# sparkfun-mlx90640-qwiic-breakout.net
KiCad netlist of a schematic drawn in EAGLE
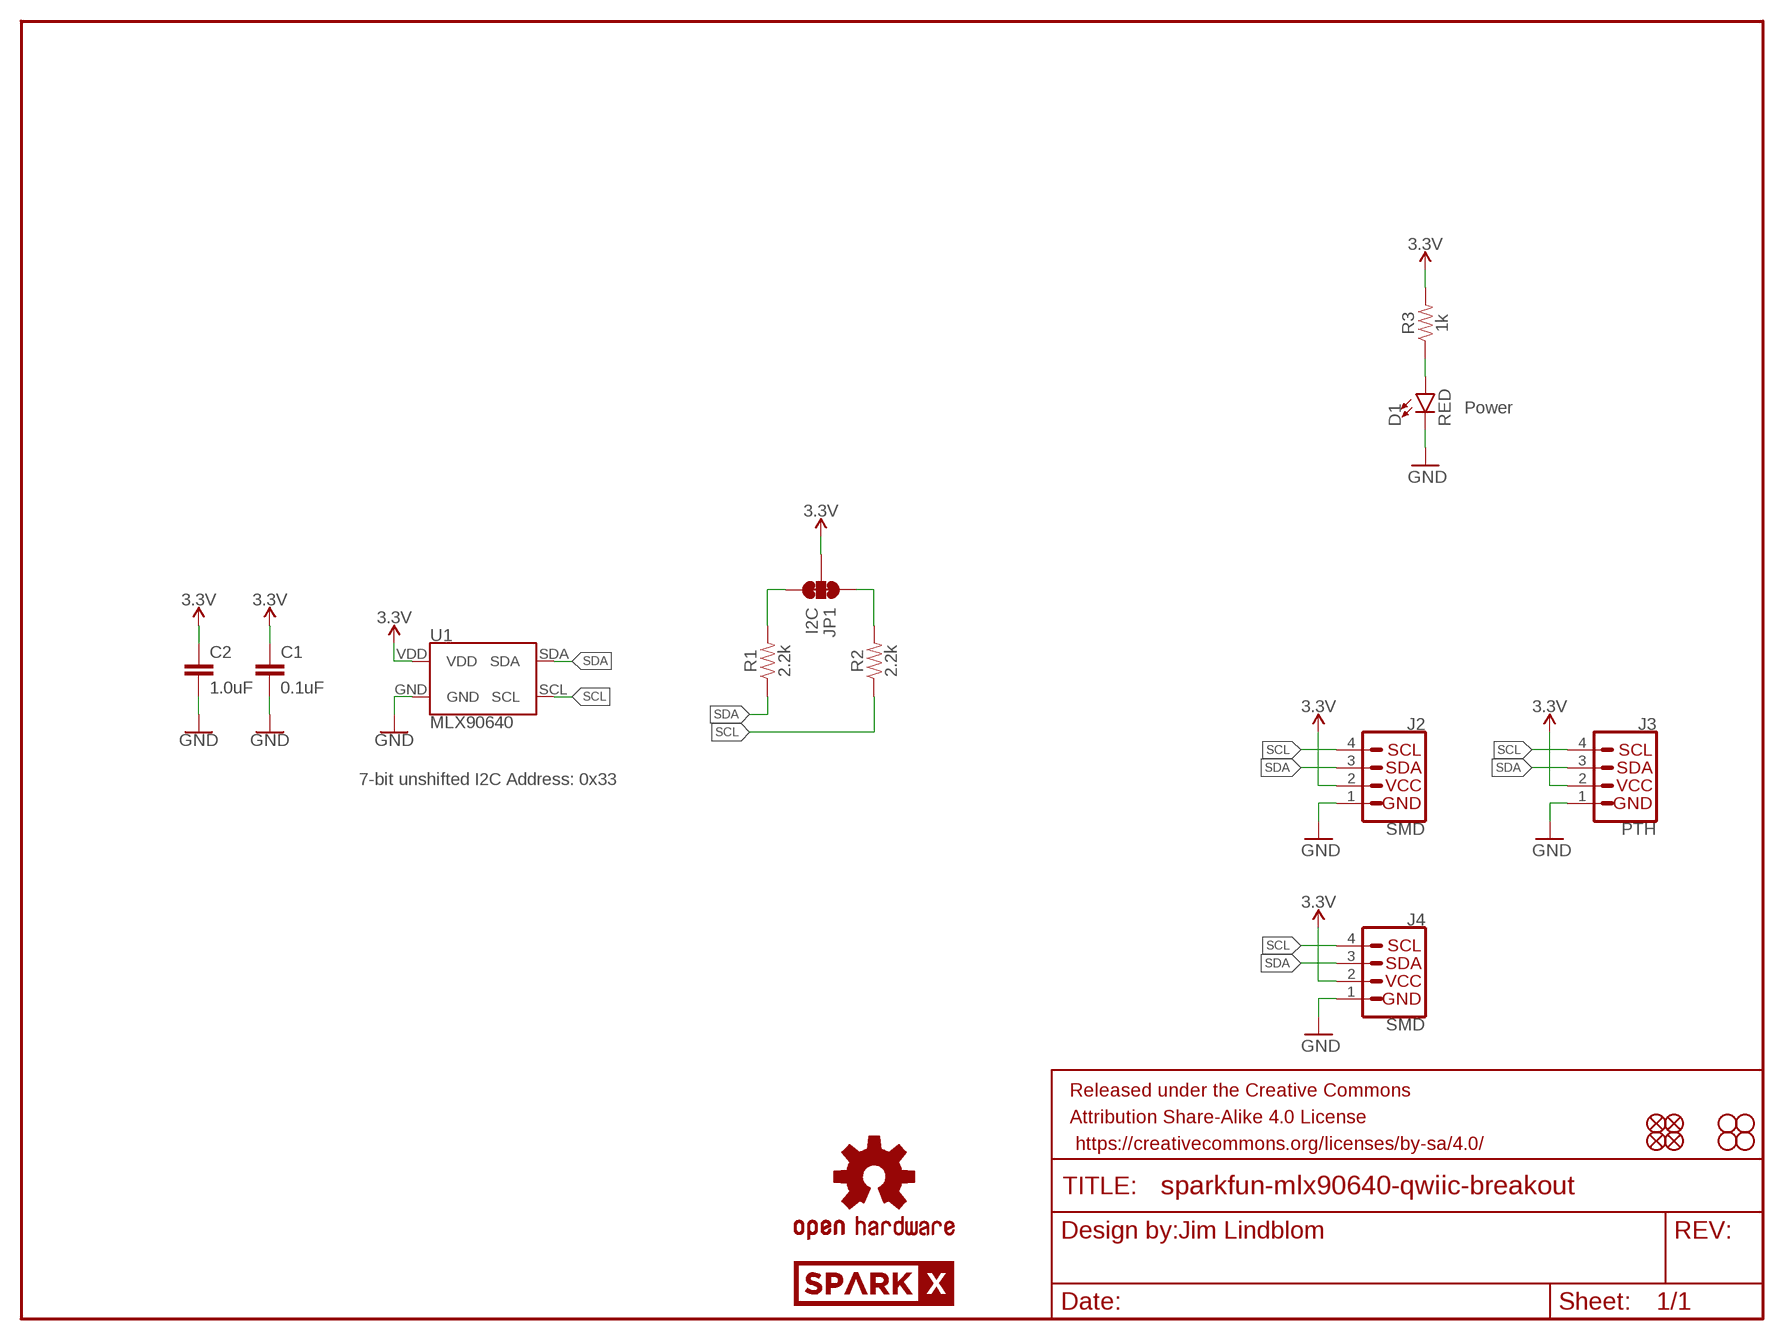
[diagram p0: schematic, sheet 1]

(export (version "E")
  (design (tool "Eeschema 10.0.6"))
  (components
    (comp (ref "C1")
      (value "0.1uF")
      (footprint "eagle-import:0603")
      (libsource (lib "eagle-import") (part "0.1UF-0603-25V-(+80/-20%)"))
    )
    (comp (ref "C2")
      (value "1.0uF")
      (footprint "eagle-import:0603")
      (libsource (lib "eagle-import") (part "1.0UF-0603-16V-10%"))
    )
    (comp (ref "D1")
      (value "RED")
      (footprint "eagle-import:LED-0603")
      (libsource (lib "eagle-import") (part "LED-RED0603"))
    )
    (comp (ref "FRAME1")
      (value "FRAME-LETTER")
      (footprint "eagle-import:CREATIVE_COMMONS")
      (libsource (lib "eagle-import") (part "FRAME-LETTER"))
    )
    (comp (ref "J2")
      (value "SMD")
      (footprint "eagle-import:1X04_1MM_RA")
      (libsource (lib "eagle-import") (part "I2C_STANDARDJS-1MM"))
    )
    (comp (ref "J3")
      (value "PTH")
      (footprint "eagle-import:1X04_NO_SILK")
      (libsource (lib "eagle-import") (part "I2C_STANDARD_NO_SILK"))
    )
    (comp (ref "J4")
      (value "SMD")
      (footprint "eagle-import:1X04_1MM_RA")
      (libsource (lib "eagle-import") (part "I2C_STANDARDJS-1MM"))
    )
    (comp (ref "JP1")
      (value "I2C")
      (footprint "eagle-import:SMT-JUMPER_3_2-NC_TRACE_NO-SILK")
      (libsource (lib "eagle-import") (part "JUMPER-SMT_3_2-NC_TRACE_NO-SILK"))
    )
    (comp (ref "JP2")
      (value "FIDUCIALUFIDUCIAL")
      (footprint "eagle-import:MICRO-FIDUCIAL")
      (libsource (lib "eagle-import") (part "FIDUCIALUFIDUCIAL"))
    )
    (comp (ref "JP3")
      (value "STAND-OFF")
      (footprint "eagle-import:STAND-OFF")
      (libsource (lib "eagle-import") (part "STAND-OFF"))
    )
    (comp (ref "JP4")
      (value "STAND-OFF")
      (footprint "eagle-import:STAND-OFF")
      (libsource (lib "eagle-import") (part "STAND-OFF"))
    )
    (comp (ref "JP5")
      (value "FIDUCIALUFIDUCIAL")
      (footprint "eagle-import:MICRO-FIDUCIAL")
      (libsource (lib "eagle-import") (part "FIDUCIALUFIDUCIAL"))
    )
    (comp (ref "JP6")
      (value "FIDUCIALUFIDUCIAL")
      (footprint "eagle-import:MICRO-FIDUCIAL")
      (libsource (lib "eagle-import") (part "FIDUCIALUFIDUCIAL"))
    )
    (comp (ref "JP7")
      (value "FIDUCIALUFIDUCIAL")
      (footprint "eagle-import:MICRO-FIDUCIAL")
      (libsource (lib "eagle-import") (part "FIDUCIALUFIDUCIAL"))
    )
    (comp (ref "JP8")
      (value "STAND-OFF")
      (footprint "eagle-import:STAND-OFF")
      (libsource (lib "eagle-import") (part "STAND-OFF"))
    )
    (comp (ref "JP9")
      (value "STAND-OFF")
      (footprint "eagle-import:STAND-OFF")
      (libsource (lib "eagle-import") (part "STAND-OFF"))
    )
    (comp (ref "LOGO1")
      (value "OSHW-LOGOMINI")
      (footprint "eagle-import:OSHW-LOGO-MINI")
      (libsource (lib "eagle-import") (part "OSHW-LOGOMINI"))
    )
    (comp (ref "R1")
      (value "2.2k")
      (footprint "eagle-import:0603")
      (libsource (lib "eagle-import") (part "2.2KOHM-0603-1/10W-1%"))
    )
    (comp (ref "R2")
      (value "2.2k")
      (footprint "eagle-import:0603")
      (libsource (lib "eagle-import") (part "2.2KOHM-0603-1/10W-1%"))
    )
    (comp (ref "R3")
      (value "1k")
      (footprint "eagle-import:0603")
      (libsource (lib "eagle-import") (part "1KOHM-0603-1/10W-1%"))
    )
    (comp (ref "U$2")
      (value "SPARKX-LOGO5")
      (footprint "eagle-import:SPARKX-LARGE")
      (libsource (lib "eagle-import") (part "SPARKX-LOGO5"))
    )
    (comp (ref "U$3")
      (value "SPARKX-LOGO4")
      (footprint "eagle-import:SPARKX-MEDIUM")
      (libsource (lib "eagle-import") (part "SPARKX-LOGO4"))
    )
    (comp (ref "U1")
      (value "MLX90640")
      (footprint "eagle-import:MLX90640")
      (libsource (lib "eagle-import") (part "MLX90640"))
    )
  )
  (nets
    (net (code "1") (name "3.3V") (class "Default")
      (node (ref "C1") (pin "1") (pinfunction "1_1") (pintype "passive"))
      (node (ref "C2") (pin "1") (pinfunction "1_1") (pintype "passive"))
      (node (ref "J2") (pin "2") (pinfunction "VCC_2") (pintype "power_in"))
      (node (ref "J3") (pin "2") (pinfunction "VCC_2") (pintype "power_in"))
      (node (ref "J4") (pin "2") (pinfunction "VCC_2") (pintype "power_in"))
      (node (ref "JP1") (pin "2") (pinfunction "2_2") (pintype "passive"))
      (node (ref "R3") (pin "2") (pinfunction "2_2") (pintype "passive"))
      (node (ref "U1") (pin "VDD") (pinfunction "VDD_VDD") (pintype "bidirectional"))
    )
    (net (code "2") (name "GND") (class "Default")
      (node (ref "C1") (pin "2") (pinfunction "2_2") (pintype "passive"))
      (node (ref "C2") (pin "2") (pinfunction "2_2") (pintype "passive"))
      (node (ref "D1") (pin "C") (pinfunction "C_C") (pintype "passive"))
      (node (ref "J2") (pin "1") (pinfunction "GND_1") (pintype "power_in"))
      (node (ref "J3") (pin "1") (pinfunction "GND_1") (pintype "power_in"))
      (node (ref "J4") (pin "1") (pinfunction "GND_1") (pintype "power_in"))
      (node (ref "U1") (pin "GND") (pinfunction "GND_GND") (pintype "bidirectional"))
    )
    (net (code "3") (name "Net-(D1-PadA)") (class "Default")
      (node (ref "D1") (pin "A") (pinfunction "A_A") (pintype "passive"))
      (node (ref "R3") (pin "1") (pinfunction "1_1") (pintype "passive"))
    )
    (net (code "4") (name "Net-(JP1-Pad1)") (class "Default")
      (node (ref "JP1") (pin "1") (pinfunction "1_1") (pintype "passive"))
      (node (ref "R2") (pin "2") (pinfunction "2_2") (pintype "passive"))
    )
    (net (code "5") (name "Net-(JP1-Pad3)") (class "Default")
      (node (ref "JP1") (pin "3") (pinfunction "3_3") (pintype "passive"))
      (node (ref "R1") (pin "2") (pinfunction "2_2") (pintype "passive"))
    )
    (net (code "6") (name "SCL") (class "Default")
      (node (ref "J2") (pin "4") (pinfunction "SCL_4") (pintype "passive"))
      (node (ref "J3") (pin "4") (pinfunction "SCL_4") (pintype "passive"))
      (node (ref "J4") (pin "4") (pinfunction "SCL_4") (pintype "passive"))
      (node (ref "R2") (pin "1") (pinfunction "1_1") (pintype "passive"))
      (node (ref "U1") (pin "SCL") (pinfunction "SCL_SCL") (pintype "bidirectional"))
    )
    (net (code "7") (name "SDA") (class "Default")
      (node (ref "J2") (pin "3") (pinfunction "SDA_3") (pintype "passive"))
      (node (ref "J3") (pin "3") (pinfunction "SDA_3") (pintype "passive"))
      (node (ref "J4") (pin "3") (pinfunction "SDA_3") (pintype "passive"))
      (node (ref "R1") (pin "1") (pinfunction "1_1") (pintype "passive"))
      (node (ref "U1") (pin "SDA") (pinfunction "SDA_SDA") (pintype "bidirectional"))
    )
  )
)
